# LPCB235_-_RM48_-_ANALOG.net
KiCad netlist of a schematic drawn in Altium Designer
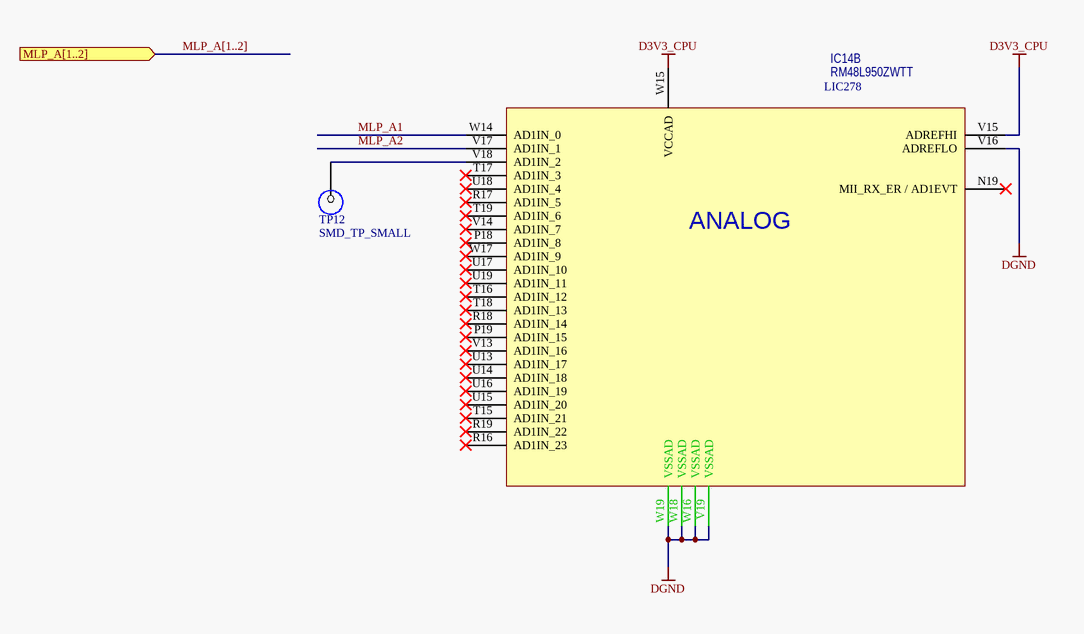
[diagram p0: LPCB235 - RM48 - ANALOG.SchDoc]

(export (version "E")
  (design (tool "Eeschema 10.0.6"))
  (components
    (comp (ref "IC14")
      (value "RM48L950ZWTT")
      (footprint "LFP054__ZWT (S-PBGA-N337)")
      (description "IC, CPU, RM48 Safety CPU, SMD NFBGA337 [LIC278]")
      (fields (field (name "LDL_NUMBER") "LIC278"))
      (libsource (lib "LDL_Semiconductors") (part "RM48L950ZWTT"))
    )
    (comp (ref "TP12")
      (value "SMD_TP_SMALL")
      (footprint "SMD-TP-SMALL")
      (description "SMD Test Point")
      (libsource (lib "LDL_Connectors") (part "SMD_TP_SMALL"))
    )
  )
  (nets
    (net (code "1") (name "/MLP_A1") (class "Default")
      (node (ref "IC14") (pin "W14") (pinfunction "AD1IN_0_W14") (pintype "passive"))
    )
    (net (code "2") (name "/MLP_A2") (class "Default")
      (node (ref "IC14") (pin "V17") (pinfunction "AD1IN_1_V17") (pintype "passive"))
    )
    (net (code "4") (name "D3V3_CPU") (class "Default")
      (node (ref "IC14") (pin "V15") (pinfunction "ADREFHI_V15") (pintype "passive"))
      (node (ref "IC14") (pin "W15") (pinfunction "VCCAD_W15") (pintype "passive"))
    )
    (net (code "5") (name "DGND") (class "Default")
      (node (ref "IC14") (pin "V16") (pinfunction "ADREFLO_V16") (pintype "passive"))
      (node (ref "IC14") (pin "V19") (pinfunction "VSSAD_V19") (pintype "passive"))
      (node (ref "IC14") (pin "W16") (pinfunction "VSSAD_W16") (pintype "passive"))
      (node (ref "IC14") (pin "W18") (pinfunction "VSSAD_W18") (pintype "passive"))
      (node (ref "IC14") (pin "W19") (pinfunction "VSSAD_W19") (pintype "passive"))
    )
    (net (code "6") (name "Net-(IC14B-AD1IN_2)") (class "Default")
      (node (ref "IC14") (pin "V18") (pinfunction "AD1IN_2_V18") (pintype "passive"))
      (node (ref "TP12") (pin "1") (pintype "passive"))
    )
    (net (code "7") (name "unconnected-(IC14B-AD1IN_3-PadT17)") (class "Default")
      (node (ref "IC14") (pin "T17") (pinfunction "AD1IN_3_T17") (pintype "passive+no_connect"))
    )
    (net (code "8") (name "unconnected-(IC14B-AD1IN_4-PadU18)") (class "Default")
      (node (ref "IC14") (pin "U18") (pinfunction "AD1IN_4_U18") (pintype "passive+no_connect"))
    )
    (net (code "9") (name "unconnected-(IC14B-AD1IN_5-PadR17)") (class "Default")
      (node (ref "IC14") (pin "R17") (pinfunction "AD1IN_5_R17") (pintype "passive+no_connect"))
    )
    (net (code "10") (name "unconnected-(IC14B-AD1IN_6-PadT19)") (class "Default")
      (node (ref "IC14") (pin "T19") (pinfunction "AD1IN_6_T19") (pintype "passive+no_connect"))
    )
    (net (code "11") (name "unconnected-(IC14B-AD1IN_7-PadV14)") (class "Default")
      (node (ref "IC14") (pin "V14") (pinfunction "AD1IN_7_V14") (pintype "passive+no_connect"))
    )
    (net (code "12") (name "unconnected-(IC14B-AD1IN_8-PadP18)") (class "Default")
      (node (ref "IC14") (pin "P18") (pinfunction "AD1IN_8_P18") (pintype "passive+no_connect"))
    )
    (net (code "13") (name "unconnected-(IC14B-AD1IN_9-PadW17)") (class "Default")
      (node (ref "IC14") (pin "W17") (pinfunction "AD1IN_9_W17") (pintype "passive+no_connect"))
    )
    (net (code "14") (name "unconnected-(IC14B-AD1IN_10-PadU17)") (class "Default")
      (node (ref "IC14") (pin "U17") (pinfunction "AD1IN_10_U17") (pintype "passive+no_connect"))
    )
    (net (code "15") (name "unconnected-(IC14B-AD1IN_11-PadU19)") (class "Default")
      (node (ref "IC14") (pin "U19") (pinfunction "AD1IN_11_U19") (pintype "passive+no_connect"))
    )
    (net (code "16") (name "unconnected-(IC14B-AD1IN_12-PadT16)") (class "Default")
      (node (ref "IC14") (pin "T16") (pinfunction "AD1IN_12_T16") (pintype "passive+no_connect"))
    )
    (net (code "17") (name "unconnected-(IC14B-AD1IN_13-PadT18)") (class "Default")
      (node (ref "IC14") (pin "T18") (pinfunction "AD1IN_13_T18") (pintype "passive+no_connect"))
    )
    (net (code "18") (name "unconnected-(IC14B-AD1IN_14-PadR18)") (class "Default")
      (node (ref "IC14") (pin "R18") (pinfunction "AD1IN_14_R18") (pintype "passive+no_connect"))
    )
    (net (code "19") (name "unconnected-(IC14B-AD1IN_15-PadP19)") (class "Default")
      (node (ref "IC14") (pin "P19") (pinfunction "AD1IN_15_P19") (pintype "passive+no_connect"))
    )
    (net (code "20") (name "unconnected-(IC14B-AD1IN_16-PadV13)") (class "Default")
      (node (ref "IC14") (pin "V13") (pinfunction "AD1IN_16_V13") (pintype "passive+no_connect"))
    )
    (net (code "21") (name "unconnected-(IC14B-AD1IN_17-PadU13)") (class "Default")
      (node (ref "IC14") (pin "U13") (pinfunction "AD1IN_17_U13") (pintype "passive+no_connect"))
    )
    (net (code "22") (name "unconnected-(IC14B-AD1IN_18-PadU14)") (class "Default")
      (node (ref "IC14") (pin "U14") (pinfunction "AD1IN_18_U14") (pintype "passive+no_connect"))
    )
    (net (code "23") (name "unconnected-(IC14B-AD1IN_19-PadU16)") (class "Default")
      (node (ref "IC14") (pin "U16") (pinfunction "AD1IN_19_U16") (pintype "passive+no_connect"))
    )
    (net (code "24") (name "unconnected-(IC14B-AD1IN_20-PadU15)") (class "Default")
      (node (ref "IC14") (pin "U15") (pinfunction "AD1IN_20_U15") (pintype "passive+no_connect"))
    )
    (net (code "25") (name "unconnected-(IC14B-AD1IN_21-PadT15)") (class "Default")
      (node (ref "IC14") (pin "T15") (pinfunction "AD1IN_21_T15") (pintype "passive+no_connect"))
    )
    (net (code "26") (name "unconnected-(IC14B-AD1IN_22-PadR19)") (class "Default")
      (node (ref "IC14") (pin "R19") (pinfunction "AD1IN_22_R19") (pintype "passive+no_connect"))
    )
    (net (code "27") (name "unconnected-(IC14B-AD1IN_23-PadR16)") (class "Default")
      (node (ref "IC14") (pin "R16") (pinfunction "AD1IN_23_R16") (pintype "passive+no_connect"))
    )
    (net (code "28") (name "unconnected-(IC14B-MII_RX_ER_{slash}_AD1EVT-PadN19)") (class "Default")
      (node (ref "IC14") (pin "N19") (pinfunction "MII_RX_ER_/_AD1EVT_N19") (pintype "passive+no_connect"))
    )
  )
)
